# FULL_WAVE_RECTIFIER_PCB_SCHEMATIC_FABRIC.net
KiCad netlist of a schematic drawn in EasyEDA
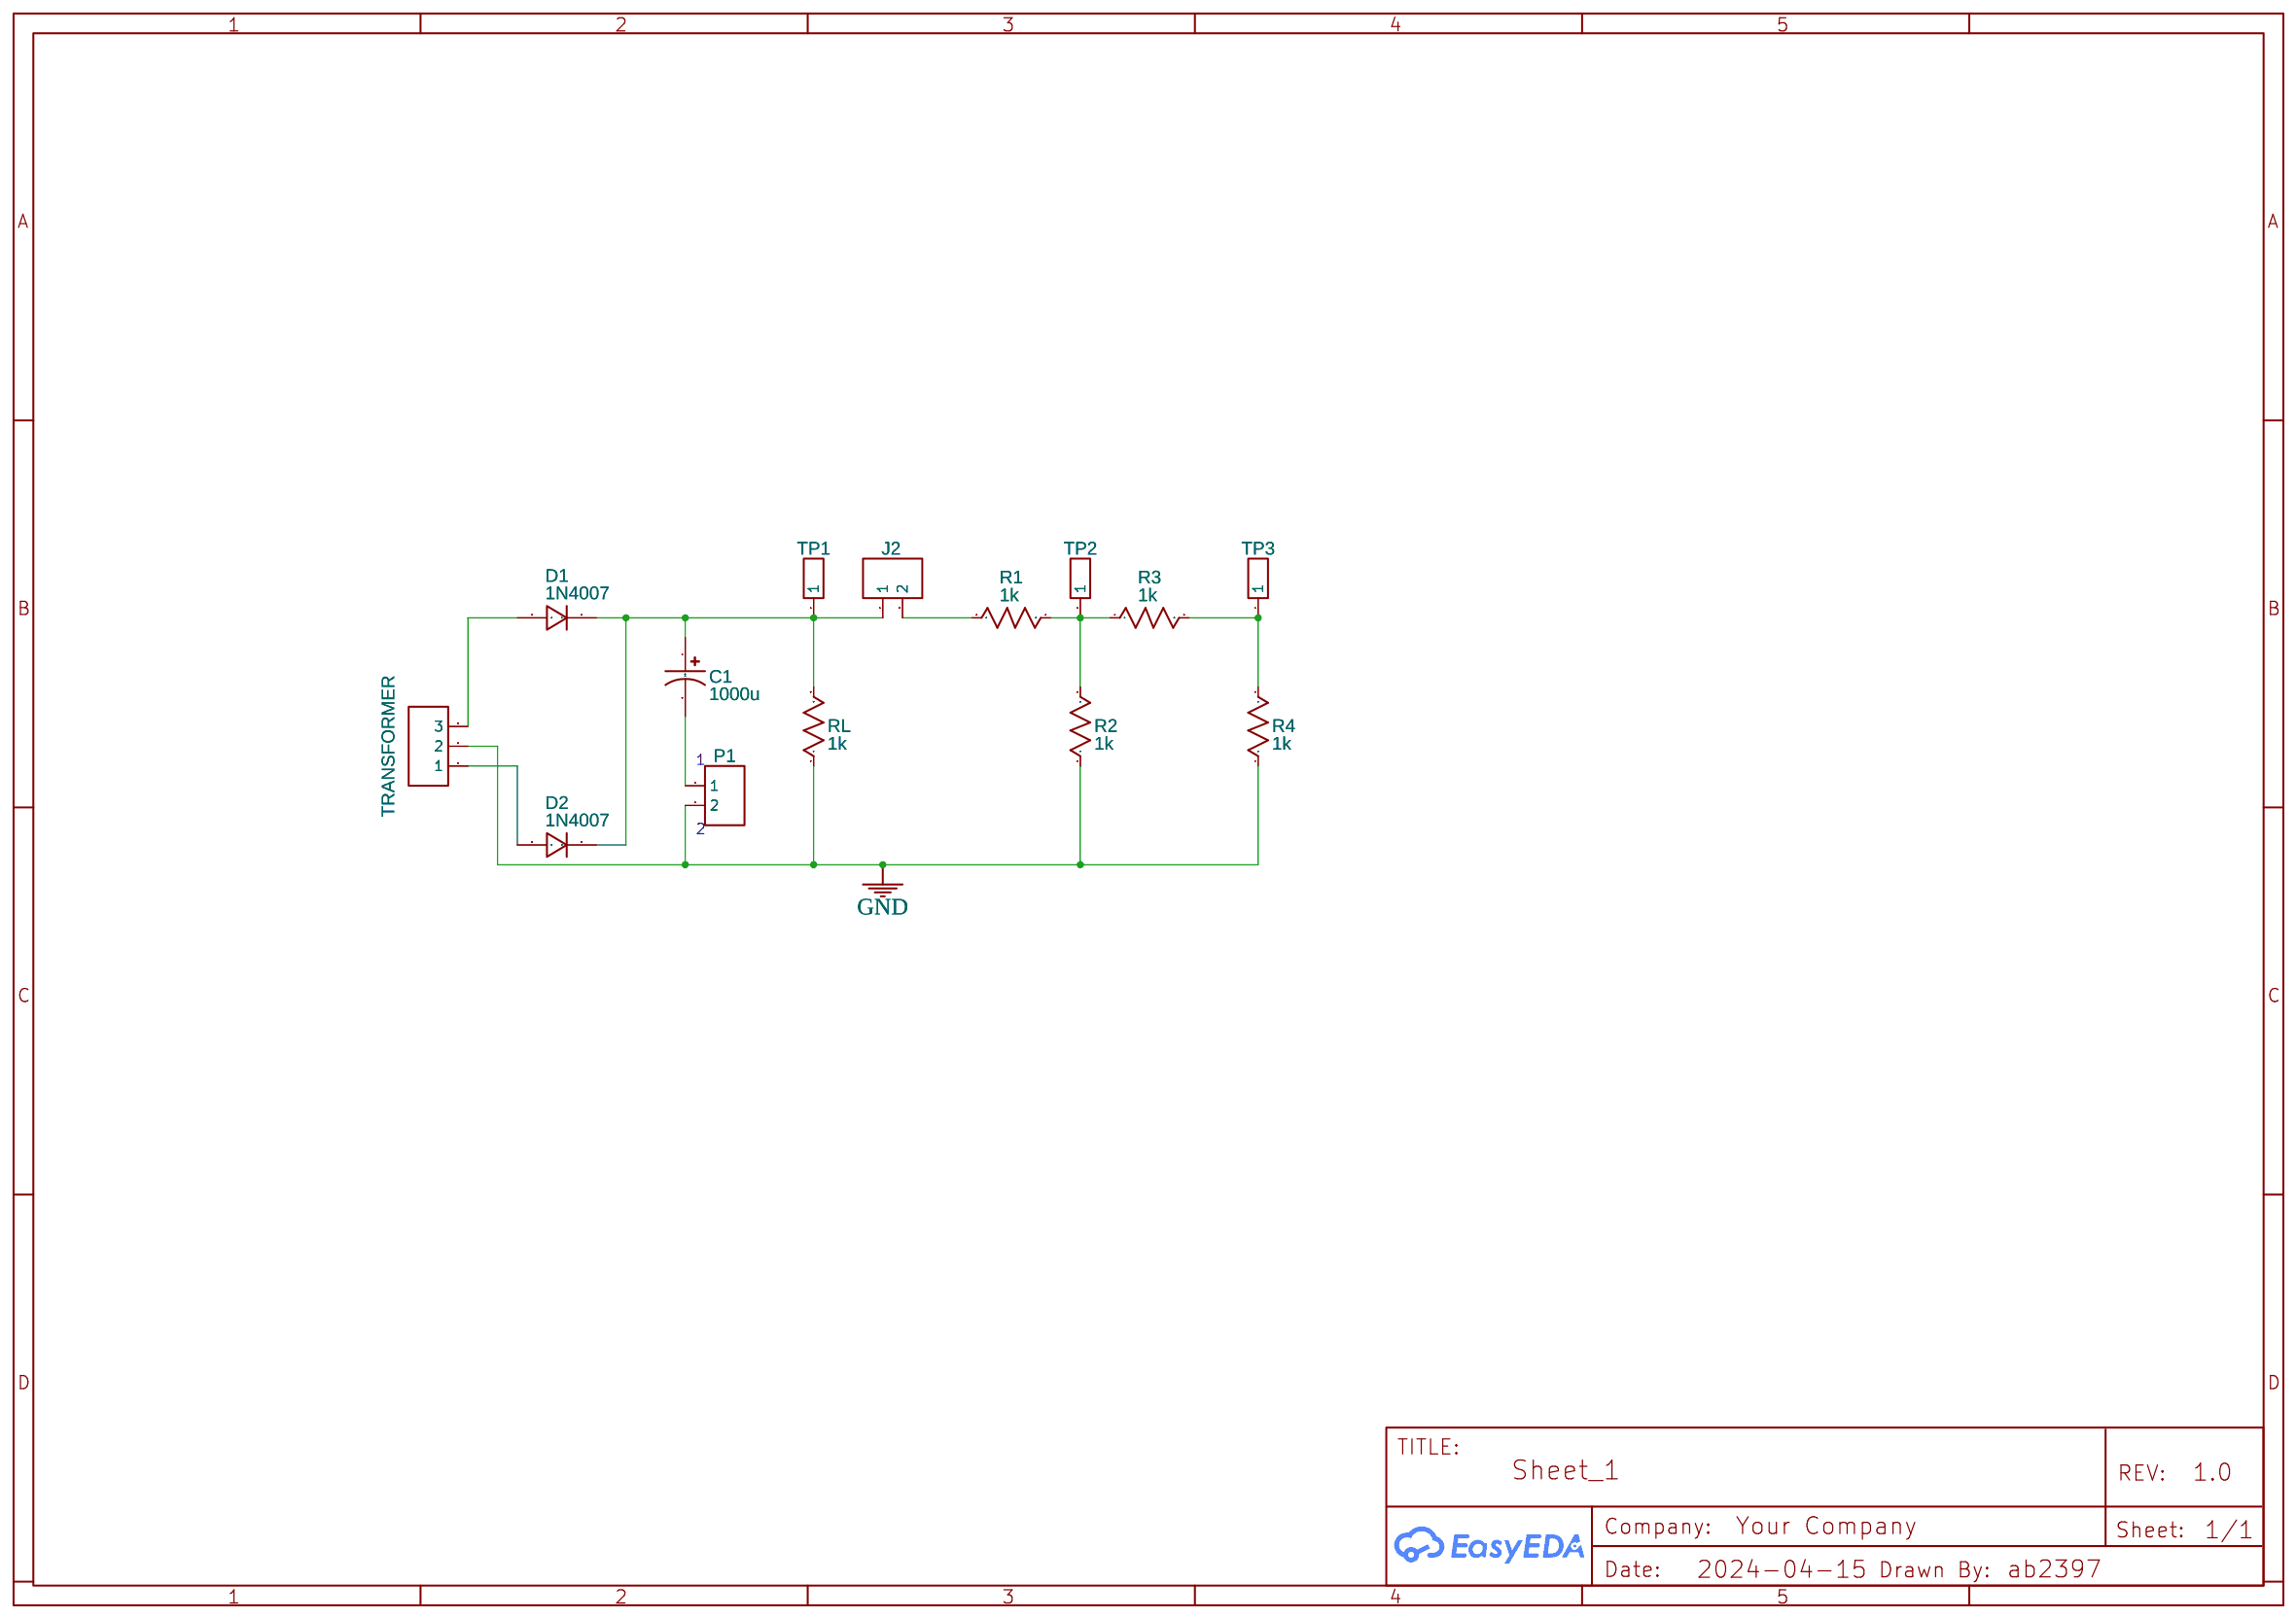
[diagram p0: schematic sheet]

(export (version "E")
  (design (tool "Eeschema 10.0.6"))
  (components
    (comp (ref "C1") (value "1000u") (libsource (lib "") (part "CE_TH_D3.0×F1.5_US")))
    (comp (ref "D1")
      (value "1N4007")
      (fields (field (name "Manufacturer") "SEMTECH"))
      (libsource (lib "") (part "1N4007"))
    )
    (comp (ref "D2")
      (value "1N4007")
      (fields (field (name "Manufacturer") "SEMTECH"))
      (libsource (lib "") (part "1N4007"))
    )
    (comp (ref "J2") (value "CONN-TH_2P-P5.00") (libsource (lib "") (part "CONN-TH_2P-P5.00")))
    (comp (ref "P1") (value "CONN-TH_2P-P5.00") (libsource (lib "") (part "CONN-TH_2P-P5.00_1")))
    (comp (ref "R1") (value "1k") (libsource (lib "") (part "R_AXIAL-0.3_US_1")))
    (comp (ref "R2") (value "1k") (libsource (lib "") (part "R_AXIAL-0.3_US")))
    (comp (ref "R3") (value "1k") (libsource (lib "") (part "R_AXIAL-0.3_US_1")))
    (comp (ref "R4") (value "1k") (libsource (lib "") (part "R_AXIAL-0.3_US")))
    (comp (ref "RL") (value "1k") (libsource (lib "") (part "R_AXIAL-0.3_US_2")))
    (comp (ref "TP1") (value "HDR-M-2.54_1x1") (libsource (lib "") (part "HDR-M-2.54_1x1")))
    (comp (ref "TP2") (value "HDR-M-2.54_1x1") (libsource (lib "") (part "HDR-M-2.54_1x1")))
    (comp (ref "TP3") (value "HDR-M-2.54_1x1") (libsource (lib "") (part "HDR-M-2.54_1x1")))
    (comp (ref "TRANSFORMER") (value "HDR-F-2.54_1x3") (libsource (lib "") (part "HDR-F-2.54_1x3")))
  )
  (nets
    (net (code "1") (name "GND") (class "Default")
      (node (ref "P1") (pin "2") (pinfunction "2_2") (pintype "unspecified"))
      (node (ref "R2") (pin "1") (pinfunction "1_1") (pintype "unspecified"))
      (node (ref "R4") (pin "1") (pinfunction "1_1") (pintype "unspecified"))
      (node (ref "RL") (pin "1") (pinfunction "1_1") (pintype "unspecified"))
      (node (ref "TRANSFORMER") (pin "2") (pinfunction "2_2") (pintype "input"))
    )
    (net (code "2") (name "Net-(C1-Pad1)") (class "Default")
      (node (ref "C1") (pin "1") (pinfunction "1_1") (pintype "unspecified"))
      (node (ref "D1") (pin "1") (pinfunction "1_1") (pintype "unspecified"))
      (node (ref "D2") (pin "1") (pinfunction "1_1") (pintype "unspecified"))
      (node (ref "J2") (pin "1") (pinfunction "1_1") (pintype "unspecified"))
      (node (ref "RL") (pin "2") (pinfunction "2_2") (pintype "unspecified"))
      (node (ref "TP1") (pin "1") (pinfunction "1_1") (pintype "input"))
    )
    (net (code "3") (name "Net-(C1-Pad2)") (class "Default")
      (node (ref "C1") (pin "2") (pinfunction "2_2") (pintype "unspecified"))
      (node (ref "P1") (pin "1") (pinfunction "1_1") (pintype "unspecified"))
    )
    (net (code "4") (name "Net-(D1-Pad2)") (class "Default")
      (node (ref "D1") (pin "2") (pinfunction "2_2") (pintype "unspecified"))
      (node (ref "TRANSFORMER") (pin "3") (pinfunction "3_3") (pintype "input"))
    )
    (net (code "5") (name "Net-(D2-Pad2)") (class "Default")
      (node (ref "D2") (pin "2") (pinfunction "2_2") (pintype "unspecified"))
      (node (ref "TRANSFORMER") (pin "1") (pinfunction "1_1") (pintype "input"))
    )
    (net (code "6") (name "Net-(J2-Pad2)") (class "Default")
      (node (ref "J2") (pin "2") (pinfunction "2_2") (pintype "unspecified"))
      (node (ref "R1") (pin "1") (pinfunction "1_1") (pintype "unspecified"))
    )
    (net (code "7") (name "Net-(R1-Pad2)") (class "Default")
      (node (ref "R1") (pin "2") (pinfunction "2_2") (pintype "unspecified"))
      (node (ref "R2") (pin "2") (pinfunction "2_2") (pintype "unspecified"))
      (node (ref "R3") (pin "1") (pinfunction "1_1") (pintype "unspecified"))
      (node (ref "TP2") (pin "1") (pinfunction "1_1") (pintype "input"))
    )
    (net (code "8") (name "Net-(R3-Pad2)") (class "Default")
      (node (ref "R3") (pin "2") (pinfunction "2_2") (pintype "unspecified"))
      (node (ref "R4") (pin "2") (pinfunction "2_2") (pintype "unspecified"))
      (node (ref "TP3") (pin "1") (pinfunction "1_1") (pintype "input"))
    )
  )
)
